# TranCT.net
KiCad netlist of a schematic drawn in EAGLE
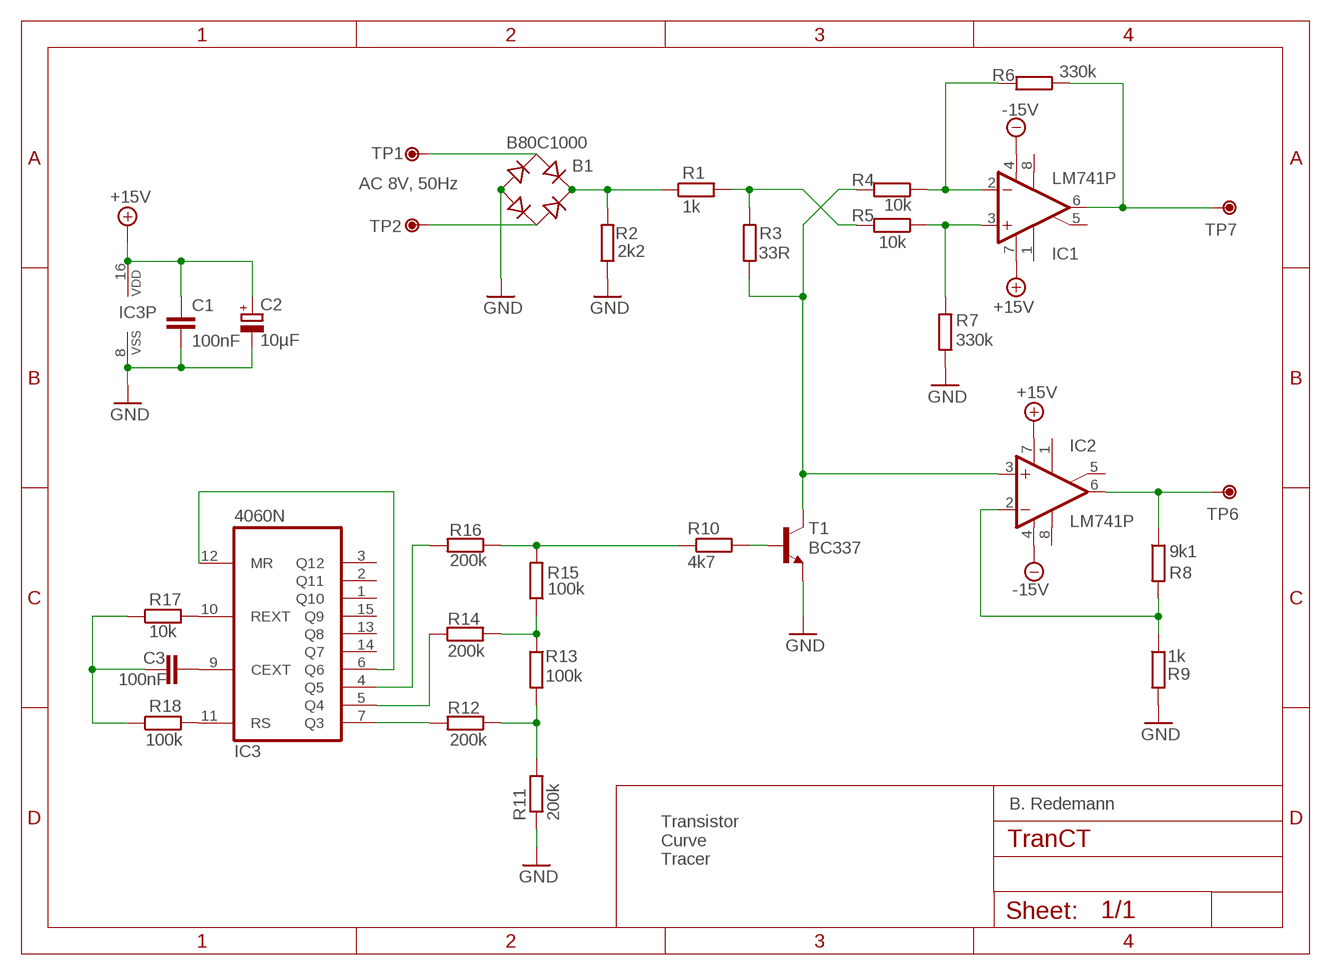
[diagram p0: schematic, sheet 1]

(export (version "E")
  (design (tool "Eeschema 10.0.6"))
  (components
    (comp (ref "B1")
      (value "B80C1000")
      (footprint "eagle-import:B-DIL")
      (libsource (lib "eagle-import") (part "B-DIL"))
    )
    (comp (ref "C1")
      (value "100nF")
      (footprint "eagle-import:C025-024X044")
      (libsource (lib "eagle-import") (part "C-EU025-024X044"))
    )
    (comp (ref "C2")
      (value "10µF")
      (footprint "eagle-import:PANASONIC_A")
      (libsource (lib "eagle-import") (part "CPOL-EUA"))
    )
    (comp (ref "C3")
      (value "100nF")
      (footprint "eagle-import:C025-024X044")
      (libsource (lib "eagle-import") (part "C-EU025-024X044"))
    )
    (comp (ref "IC1")
      (value "LM741P")
      (footprint "eagle-import:DIL08")
      (libsource (lib "eagle-import") (part "741PLM"))
    )
    (comp (ref "IC2")
      (value "LM741P")
      (footprint "eagle-import:DIL08")
      (libsource (lib "eagle-import") (part "741PLM"))
    )
    (comp (ref "IC3")
      (value "4060N")
      (footprint "eagle-import:DIL16")
      (libsource (lib "eagle-import") (part "4060N"))
    )
    (comp (ref "R1")
      (value "1k")
      (footprint "eagle-import:0204_7")
      (libsource (lib "eagle-import") (part "R-EU_0204/7"))
    )
    (comp (ref "R2")
      (value "2k2")
      (footprint "eagle-import:0204_7")
      (libsource (lib "eagle-import") (part "R-EU_0204/7"))
    )
    (comp (ref "R3")
      (value "33R")
      (footprint "eagle-import:0204_7")
      (libsource (lib "eagle-import") (part "R-EU_0204/7"))
    )
    (comp (ref "R4")
      (value "10k")
      (footprint "eagle-import:0204_7")
      (libsource (lib "eagle-import") (part "R-EU_0204/7"))
    )
    (comp (ref "R5")
      (value "10k")
      (footprint "eagle-import:0204_7")
      (libsource (lib "eagle-import") (part "R-EU_0204/7"))
    )
    (comp (ref "R6")
      (value "330k")
      (footprint "eagle-import:0204_7")
      (libsource (lib "eagle-import") (part "R-EU_0204/7"))
    )
    (comp (ref "R7")
      (value "330k")
      (footprint "eagle-import:0204_7")
      (libsource (lib "eagle-import") (part "R-EU_0204/7"))
    )
    (comp (ref "R8")
      (value "9k1")
      (footprint "eagle-import:0204_7")
      (libsource (lib "eagle-import") (part "R-EU_0204/7"))
    )
    (comp (ref "R9")
      (value "1k")
      (footprint "eagle-import:0204_7")
      (libsource (lib "eagle-import") (part "R-EU_0204/7"))
    )
    (comp (ref "R10")
      (value "4k7")
      (footprint "eagle-import:0204_7")
      (libsource (lib "eagle-import") (part "R-EU_0204/7"))
    )
    (comp (ref "R11")
      (value "200k")
      (footprint "eagle-import:0204_7")
      (libsource (lib "eagle-import") (part "R-EU_0204/7"))
    )
    (comp (ref "R12")
      (value "200k")
      (footprint "eagle-import:0204_7")
      (libsource (lib "eagle-import") (part "R-EU_0204/7"))
    )
    (comp (ref "R13")
      (value "100k")
      (footprint "eagle-import:0204_7")
      (libsource (lib "eagle-import") (part "R-EU_0204/7"))
    )
    (comp (ref "R14")
      (value "200k")
      (footprint "eagle-import:0204_7")
      (libsource (lib "eagle-import") (part "R-EU_0204/7"))
    )
    (comp (ref "R15")
      (value "100k")
      (footprint "eagle-import:0204_7")
      (libsource (lib "eagle-import") (part "R-EU_0204/7"))
    )
    (comp (ref "R16")
      (value "200k")
      (footprint "eagle-import:0204_7")
      (libsource (lib "eagle-import") (part "R-EU_0204/7"))
    )
    (comp (ref "R17")
      (value "10k")
      (footprint "eagle-import:0204_7")
      (libsource (lib "eagle-import") (part "R-EU_0204/7"))
    )
    (comp (ref "R18")
      (value "100k")
      (footprint "eagle-import:0204_7")
      (libsource (lib "eagle-import") (part "R-EU_0204/7"))
    )
    (comp (ref "T1")
      (value "BC337")
      (footprint "eagle-import:TO92")
      (libsource (lib "eagle-import") (part "BC337"))
    )
    (comp (ref "TP1")
      (value "TPB1,27")
      (footprint "eagle-import:B1,27")
      (libsource (lib "eagle-import") (part "TPB1,27"))
    )
    (comp (ref "TP2")
      (value "TPB1,27")
      (footprint "eagle-import:B1,27")
      (libsource (lib "eagle-import") (part "TPB1,27"))
    )
    (comp (ref "TP6")
      (value "TPB1,27")
      (footprint "eagle-import:B1,27")
      (libsource (lib "eagle-import") (part "TPB1,27"))
    )
    (comp (ref "TP7")
      (value "TPB1,27")
      (footprint "eagle-import:B1,27")
      (libsource (lib "eagle-import") (part "TPB1,27"))
    )
  )
  (nets
    (net (code "1") (name "+15V") (class "Default")
      (node (ref "C1") (pin "1") (pinfunction "1_1") (pintype "passive"))
      (node (ref "C2") (pin "+") (pinfunction "+_+") (pintype "passive"))
      (node (ref "IC1") (pin "7") (pinfunction "V+_7") (pintype "power_in"))
      (node (ref "IC2") (pin "7") (pinfunction "V+_7") (pintype "power_in"))
      (node (ref "IC3") (pin "16") (pinfunction "VDD_16") (pintype "power_in"))
    )
    (net (code "2") (name "-15V") (class "Default")
      (node (ref "IC1") (pin "4") (pinfunction "V-_4") (pintype "power_in"))
      (node (ref "IC2") (pin "4") (pinfunction "V-_4") (pintype "power_in"))
    )
    (net (code "3") (name "GND") (class "Default")
      (node (ref "B1") (pin "-") (pinfunction "-_-") (pintype "passive"))
      (node (ref "C1") (pin "2") (pinfunction "2_2") (pintype "passive"))
      (node (ref "C2") (pin "-") (pinfunction "-_-") (pintype "passive"))
      (node (ref "IC3") (pin "8") (pinfunction "VSS_8") (pintype "power_in"))
      (node (ref "R11") (pin "1") (pinfunction "1_1") (pintype "passive"))
      (node (ref "R2") (pin "1") (pinfunction "1_1") (pintype "passive"))
      (node (ref "R7") (pin "2") (pinfunction "2_2") (pintype "passive"))
      (node (ref "R9") (pin "2") (pinfunction "2_2") (pintype "passive"))
      (node (ref "T1") (pin "1") (pinfunction "E_1") (pintype "passive"))
    )
    (net (code "4") (name "Net-(B1-Pad+)") (class "Default")
      (node (ref "B1") (pin "+") (pinfunction "+_+") (pintype "passive"))
      (node (ref "R1") (pin "1") (pinfunction "1_1") (pintype "passive"))
      (node (ref "R2") (pin "2") (pinfunction "2_2") (pintype "passive"))
    )
    (net (code "5") (name "Net-(B1-PadAC1)") (class "Default")
      (node (ref "B1") (pin "AC1") (pinfunction "AC1_AC1") (pintype "passive"))
      (node (ref "TP1") (pin "TP") (pinfunction "TP_TP") (pintype "bidirectional"))
    )
    (net (code "6") (name "Net-(B1-PadAC2)") (class "Default")
      (node (ref "B1") (pin "AC2") (pinfunction "AC2_AC2") (pintype "passive"))
      (node (ref "TP2") (pin "TP") (pinfunction "TP_TP") (pintype "bidirectional"))
    )
    (net (code "7") (name "Net-(C3-Pad1)") (class "Default")
      (node (ref "C3") (pin "1") (pinfunction "1_1") (pintype "passive"))
      (node (ref "R17") (pin "1") (pinfunction "1_1") (pintype "passive"))
      (node (ref "R18") (pin "1") (pinfunction "1_1") (pintype "passive"))
    )
    (net (code "8") (name "Net-(IC1-+IN)") (class "Default")
      (node (ref "IC1") (pin "3") (pinfunction "+IN_3") (pintype "input"))
      (node (ref "R5") (pin "1") (pinfunction "1_1") (pintype "passive"))
      (node (ref "R7") (pin "1") (pinfunction "1_1") (pintype "passive"))
    )
    (net (code "9") (name "Net-(IC1--IN)") (class "Default")
      (node (ref "IC1") (pin "2") (pinfunction "-IN_2") (pintype "input"))
      (node (ref "R4") (pin "1") (pinfunction "1_1") (pintype "passive"))
      (node (ref "R6") (pin "2") (pinfunction "2_2") (pintype "passive"))
    )
    (net (code "10") (name "Net-(IC1-OUT)") (class "Default")
      (node (ref "IC1") (pin "6") (pinfunction "OUT_6") (pintype "output"))
      (node (ref "R6") (pin "1") (pinfunction "1_1") (pintype "passive"))
      (node (ref "TP7") (pin "TP") (pinfunction "TP_TP") (pintype "bidirectional"))
    )
    (net (code "11") (name "Net-(IC2-+IN)") (class "Default")
      (node (ref "IC2") (pin "3") (pinfunction "+IN_3") (pintype "input"))
      (node (ref "R3") (pin "1") (pinfunction "1_1") (pintype "passive"))
      (node (ref "R4") (pin "2") (pinfunction "2_2") (pintype "passive"))
      (node (ref "T1") (pin "3") (pinfunction "C_3") (pintype "passive"))
    )
    (net (code "12") (name "Net-(IC2--IN)") (class "Default")
      (node (ref "IC2") (pin "2") (pinfunction "-IN_2") (pintype "input"))
      (node (ref "R8") (pin "2") (pinfunction "2_2") (pintype "passive"))
      (node (ref "R9") (pin "1") (pinfunction "1_1") (pintype "passive"))
    )
    (net (code "13") (name "Net-(IC2-OUT)") (class "Default")
      (node (ref "IC2") (pin "6") (pinfunction "OUT_6") (pintype "output"))
      (node (ref "R8") (pin "1") (pinfunction "1_1") (pintype "passive"))
      (node (ref "TP6") (pin "TP") (pinfunction "TP_TP") (pintype "bidirectional"))
    )
    (net (code "14") (name "Net-(IC3A-CEXT)") (class "Default")
      (node (ref "C3") (pin "2") (pinfunction "2_2") (pintype "passive"))
      (node (ref "IC3") (pin "9") (pinfunction "CEXT_9") (pintype "output"))
    )
    (net (code "15") (name "Net-(IC3A-MR)") (class "Default")
      (node (ref "IC3") (pin "12") (pinfunction "MR_12") (pintype "input"))
      (node (ref "IC3") (pin "6") (pinfunction "Q6_6") (pintype "output"))
    )
    (net (code "16") (name "Net-(IC3A-Q3)") (class "Default")
      (node (ref "IC3") (pin "7") (pinfunction "Q3_7") (pintype "output"))
      (node (ref "R12") (pin "2") (pinfunction "2_2") (pintype "passive"))
    )
    (net (code "17") (name "Net-(IC3A-Q4)") (class "Default")
      (node (ref "IC3") (pin "5") (pinfunction "Q4_5") (pintype "output"))
      (node (ref "R14") (pin "1") (pinfunction "1_1") (pintype "passive"))
    )
    (net (code "18") (name "Net-(IC3A-Q5)") (class "Default")
      (node (ref "IC3") (pin "4") (pinfunction "Q5_4") (pintype "output"))
      (node (ref "R16") (pin "2") (pinfunction "2_2") (pintype "passive"))
    )
    (net (code "19") (name "Net-(IC3A-REXT)") (class "Default")
      (node (ref "IC3") (pin "10") (pinfunction "REXT_10") (pintype "output"))
      (node (ref "R17") (pin "2") (pinfunction "2_2") (pintype "passive"))
    )
    (net (code "20") (name "Net-(IC3A-RS)") (class "Default")
      (node (ref "IC3") (pin "11") (pinfunction "RS_11") (pintype "input"))
      (node (ref "R18") (pin "2") (pinfunction "2_2") (pintype "passive"))
    )
    (net (code "21") (name "Net-(R1-Pad2)") (class "Default")
      (node (ref "R1") (pin "2") (pinfunction "2_2") (pintype "passive"))
      (node (ref "R3") (pin "2") (pinfunction "2_2") (pintype "passive"))
      (node (ref "R5") (pin "2") (pinfunction "2_2") (pintype "passive"))
    )
    (net (code "22") (name "Net-(R10-Pad1)") (class "Default")
      (node (ref "R10") (pin "1") (pinfunction "1_1") (pintype "passive"))
      (node (ref "R15") (pin "2") (pinfunction "2_2") (pintype "passive"))
      (node (ref "R16") (pin "1") (pinfunction "1_1") (pintype "passive"))
    )
    (net (code "23") (name "Net-(R11-Pad2)") (class "Default")
      (node (ref "R11") (pin "2") (pinfunction "2_2") (pintype "passive"))
      (node (ref "R12") (pin "1") (pinfunction "1_1") (pintype "passive"))
      (node (ref "R13") (pin "2") (pinfunction "2_2") (pintype "passive"))
    )
    (net (code "24") (name "Net-(R13-Pad1)") (class "Default")
      (node (ref "R13") (pin "1") (pinfunction "1_1") (pintype "passive"))
      (node (ref "R14") (pin "2") (pinfunction "2_2") (pintype "passive"))
      (node (ref "R15") (pin "1") (pinfunction "1_1") (pintype "passive"))
    )
    (net (code "25") (name "Net-(T1-B)") (class "Default")
      (node (ref "R10") (pin "2") (pinfunction "2_2") (pintype "passive"))
      (node (ref "T1") (pin "2") (pinfunction "B_2") (pintype "passive"))
    )
    (net (code "26") (name "unconnected-(IC1-ON1-Pad1)") (class "Default")
      (node (ref "IC1") (pin "1") (pinfunction "ON1_1") (pintype "passive"))
    )
    (net (code "27") (name "unconnected-(IC1-ON2-Pad5)") (class "Default")
      (node (ref "IC1") (pin "5") (pinfunction "ON2_5") (pintype "passive"))
    )
    (net (code "28") (name "unconnected-(IC1-OPT-Pad8)") (class "Default")
      (node (ref "IC1") (pin "8") (pinfunction "OPT_8") (pintype "passive"))
    )
    (net (code "29") (name "unconnected-(IC2-ON1-Pad1)") (class "Default")
      (node (ref "IC2") (pin "1") (pinfunction "ON1_1") (pintype "passive"))
    )
    (net (code "30") (name "unconnected-(IC2-ON2-Pad5)") (class "Default")
      (node (ref "IC2") (pin "5") (pinfunction "ON2_5") (pintype "passive"))
    )
    (net (code "31") (name "unconnected-(IC2-OPT-Pad8)") (class "Default")
      (node (ref "IC2") (pin "8") (pinfunction "OPT_8") (pintype "passive"))
    )
    (net (code "32") (name "unconnected-(IC3A-Q7-Pad14)") (class "Default")
      (node (ref "IC3") (pin "14") (pinfunction "Q7_14") (pintype "output"))
    )
    (net (code "33") (name "unconnected-(IC3A-Q8-Pad13)") (class "Default")
      (node (ref "IC3") (pin "13") (pinfunction "Q8_13") (pintype "output"))
    )
    (net (code "34") (name "unconnected-(IC3A-Q9-Pad15)") (class "Default")
      (node (ref "IC3") (pin "15") (pinfunction "Q9_15") (pintype "output"))
    )
    (net (code "35") (name "unconnected-(IC3A-Q10-Pad1)") (class "Default")
      (node (ref "IC3") (pin "1") (pinfunction "Q10_1") (pintype "output"))
    )
    (net (code "36") (name "unconnected-(IC3A-Q11-Pad2)") (class "Default")
      (node (ref "IC3") (pin "2") (pinfunction "Q11_2") (pintype "output"))
    )
    (net (code "37") (name "unconnected-(IC3A-Q12-Pad3)") (class "Default")
      (node (ref "IC3") (pin "3") (pinfunction "Q12_3") (pintype "output"))
    )
  )
)
